# simple_board.net
KiCad netlist of a schematic drawn in EAGLE
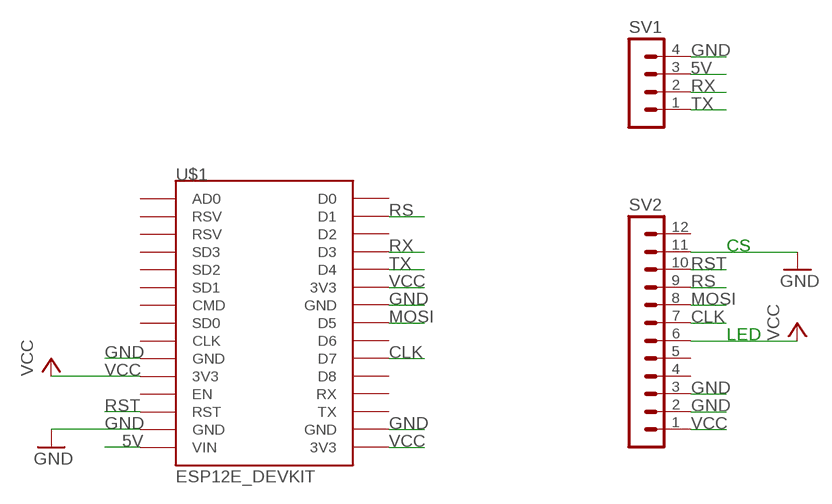
[diagram p0: schematic, sheet 1]

(export (version "E")
  (design (tool "Eeschema 10.0.6"))
  (components
    (comp (ref "SV1")
      (value "MA04-1")
      (footprint "eagle-import:MA04-1")
      (libsource (lib "eagle-import") (part "MA04-1"))
    )
    (comp (ref "SV2")
      (value "MA12-1")
      (footprint "eagle-import:MA12-1")
      (libsource (lib "eagle-import") (part "MA12-1"))
    )
    (comp (ref "U$1")
      (value "ESP12E_DEVKIT")
      (footprint "eagle-import:ESP12E_DEVKIT")
      (libsource (lib "eagle-import") (part "ESP12E_DEVKIT"))
    )
  )
  (nets
    (net (code "1") (name "/5V") (class "Default")
      (node (ref "SV1") (pin "3") (pinfunction "3_3") (pintype "passive"))
      (node (ref "U$1") (pin "VIN") (pinfunction "VIN_VIN") (pintype "bidirectional"))
    )
    (net (code "2") (name "/CLK") (class "Default")
      (node (ref "SV2") (pin "7") (pinfunction "7_7") (pintype "passive"))
      (node (ref "U$1") (pin "D7") (pinfunction "D7_D7") (pintype "bidirectional"))
    )
    (net (code "3") (name "/MOSI") (class "Default")
      (node (ref "SV2") (pin "8") (pinfunction "8_8") (pintype "passive"))
      (node (ref "U$1") (pin "D5") (pinfunction "D5_D5") (pintype "bidirectional"))
    )
    (net (code "4") (name "/RS") (class "Default")
      (node (ref "SV2") (pin "9") (pinfunction "9_9") (pintype "passive"))
      (node (ref "U$1") (pin "D1") (pinfunction "D1_D1") (pintype "bidirectional"))
    )
    (net (code "5") (name "/RST") (class "Default")
      (node (ref "SV2") (pin "10") (pinfunction "10_10") (pintype "passive"))
      (node (ref "U$1") (pin "RST") (pinfunction "RST_RST") (pintype "bidirectional"))
    )
    (net (code "6") (name "/RX") (class "Default")
      (node (ref "SV1") (pin "2") (pinfunction "2_2") (pintype "passive"))
      (node (ref "U$1") (pin "D3") (pinfunction "D3_D3") (pintype "bidirectional"))
    )
    (net (code "7") (name "/TX") (class "Default")
      (node (ref "SV1") (pin "1") (pinfunction "1_1") (pintype "passive"))
      (node (ref "U$1") (pin "D4") (pinfunction "D4_D4") (pintype "bidirectional"))
    )
    (net (code "8") (name "GND") (class "Default")
      (node (ref "SV1") (pin "4") (pinfunction "4_4") (pintype "passive"))
      (node (ref "SV2") (pin "11") (pinfunction "11_11") (pintype "passive"))
      (node (ref "SV2") (pin "2") (pinfunction "2_2") (pintype "passive"))
      (node (ref "SV2") (pin "3") (pinfunction "3_3") (pintype "passive"))
      (node (ref "U$1") (pin "GND@0") (pinfunction "GND_GND@0") (pintype "bidirectional"))
      (node (ref "U$1") (pin "GND@1") (pinfunction "GND_GND@1") (pintype "bidirectional"))
      (node (ref "U$1") (pin "GND@2") (pinfunction "GND_GND@2") (pintype "bidirectional"))
      (node (ref "U$1") (pin "GND@3") (pinfunction "GND_GND@3") (pintype "bidirectional"))
    )
    (net (code "9") (name "VCC") (class "Default")
      (node (ref "SV2") (pin "1") (pinfunction "1_1") (pintype "passive"))
      (node (ref "SV2") (pin "6") (pinfunction "6_6") (pintype "passive"))
      (node (ref "U$1") (pin "3V3@0") (pinfunction "3V3_3V3@0") (pintype "bidirectional"))
      (node (ref "U$1") (pin "3V3@1") (pinfunction "3V3_3V3@1") (pintype "bidirectional"))
      (node (ref "U$1") (pin "3V3@2") (pinfunction "3V3_3V3@2") (pintype "bidirectional"))
    )
    (net (code "10") (name "unconnected-(SV2-Pad4)") (class "Default")
      (node (ref "SV2") (pin "4") (pinfunction "4_4") (pintype "passive"))
    )
    (net (code "11") (name "unconnected-(SV2-Pad5)") (class "Default")
      (node (ref "SV2") (pin "5") (pinfunction "5_5") (pintype "passive"))
    )
    (net (code "12") (name "unconnected-(SV2-Pad12)") (class "Default")
      (node (ref "SV2") (pin "12") (pinfunction "12_12") (pintype "passive"))
    )
    (net (code "13") (name "unconnected-(U$1-PadAD0)") (class "Default")
      (node (ref "U$1") (pin "AD0") (pinfunction "AD0_AD0") (pintype "bidirectional"))
    )
    (net (code "14") (name "unconnected-(U$1-PadCLK)") (class "Default")
      (node (ref "U$1") (pin "CLK") (pinfunction "CLK_CLK") (pintype "bidirectional"))
    )
    (net (code "15") (name "unconnected-(U$1-PadCMD)") (class "Default")
      (node (ref "U$1") (pin "CMD") (pinfunction "CMD_CMD") (pintype "bidirectional"))
    )
    (net (code "16") (name "unconnected-(U$1-PadD0)") (class "Default")
      (node (ref "U$1") (pin "D0") (pinfunction "D0_D0") (pintype "bidirectional"))
    )
    (net (code "17") (name "unconnected-(U$1-PadD2)") (class "Default")
      (node (ref "U$1") (pin "D2") (pinfunction "D2_D2") (pintype "bidirectional"))
    )
    (net (code "18") (name "unconnected-(U$1-PadD6)") (class "Default")
      (node (ref "U$1") (pin "D6") (pinfunction "D6_D6") (pintype "bidirectional"))
    )
    (net (code "19") (name "unconnected-(U$1-PadD8)") (class "Default")
      (node (ref "U$1") (pin "D8") (pinfunction "D8_D8") (pintype "bidirectional"))
    )
    (net (code "20") (name "unconnected-(U$1-PadEN)") (class "Default")
      (node (ref "U$1") (pin "EN") (pinfunction "EN_EN") (pintype "bidirectional"))
    )
    (net (code "21") (name "unconnected-(U$1-PadRX)") (class "Default")
      (node (ref "U$1") (pin "RX") (pinfunction "RX_RX") (pintype "bidirectional"))
    )
    (net (code "22") (name "unconnected-(U$1-PadSD0)") (class "Default")
      (node (ref "U$1") (pin "SD0") (pinfunction "SD0_SD0") (pintype "bidirectional"))
    )
    (net (code "23") (name "unconnected-(U$1-PadSD1)") (class "Default")
      (node (ref "U$1") (pin "SD1") (pinfunction "SD1_SD1") (pintype "bidirectional"))
    )
    (net (code "24") (name "unconnected-(U$1-PadSD2)") (class "Default")
      (node (ref "U$1") (pin "SD2") (pinfunction "SD2_SD2") (pintype "bidirectional"))
    )
    (net (code "25") (name "unconnected-(U$1-PadSD3)") (class "Default")
      (node (ref "U$1") (pin "SD3") (pinfunction "SD3_SD3") (pintype "bidirectional"))
    )
    (net (code "26") (name "unconnected-(U$1-PadTX)") (class "Default")
      (node (ref "U$1") (pin "TX") (pinfunction "TX_TX") (pintype "bidirectional"))
    )
    (net (code "27") (name "unconnected-(U$1-RSV-PadRSV@0)") (class "Default")
      (node (ref "U$1") (pin "RSV@0") (pinfunction "RSV_RSV@0") (pintype "bidirectional"))
    )
    (net (code "28") (name "unconnected-(U$1-RSV-PadRSV@1)") (class "Default")
      (node (ref "U$1") (pin "RSV@1") (pinfunction "RSV_RSV@1") (pintype "bidirectional"))
    )
  )
)
